# buffer.net
KiCad netlist of a schematic drawn in Altium Designer
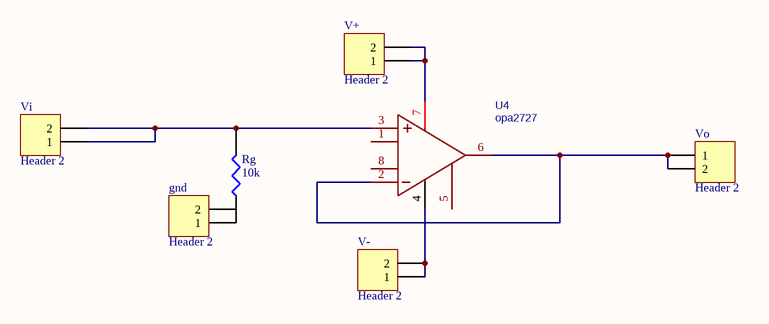
[diagram p0: buffer.SchDoc]

(export (version "E")
  (design (tool "Eeschema 10.0.6"))
  (components
    (comp (ref "gnd")
      (value "Header 2")
      (footprint "SIP2")
      (description "Header, 2-Pin")
      (fields (field (name "PUBLISHER") "Altium Limited"))
      (libsource (lib "Miscellaneous Connectors") (part "Header 2"))
    )
    (comp (ref "Rg")
      (value "10k")
      (footprint "AXIAL0.4")
      (libsource (lib "Miscellaneous Devices") (part "RES1"))
    )
    (comp (ref "U4")
      (value "opa2727")
      (footprint "DIP8")
      (fields (field (name "BOM_MANUFACTURER PART") "AD620ANZ") (field (name "BOM_SUPPLIER PART") "C9680"))
      (libsource (lib "AD620ANZ") (part "AD620ANZ"))
    )
    (comp (ref "V+")
      (value "Header 2")
      (footprint "SIP2")
      (description "Header, 2-Pin")
      (fields (field (name "PUBLISHER") "Altium Limited"))
      (libsource (lib "Miscellaneous Connectors") (part "Header 2"))
    )
    (comp (ref "V-")
      (value "Header 2")
      (footprint "SIP2")
      (description "Header, 2-Pin")
      (fields (field (name "PUBLISHER") "Altium Limited"))
      (libsource (lib "Miscellaneous Connectors") (part "Header 2"))
    )
    (comp (ref "Vi")
      (value "Header 2")
      (footprint "SIP2")
      (description "Header, 2-Pin")
      (fields (field (name "PUBLISHER") "Altium Limited"))
      (libsource (lib "Miscellaneous Connectors") (part "Header 2"))
    )
    (comp (ref "Vo")
      (value "Header 2")
      (footprint "SIP2")
      (description "Header, 2-Pin")
      (fields (field (name "PUBLISHER") "Altium Limited"))
      (libsource (lib "") (part "Header 2_1"))
    )
  )
  (nets
    (net (code "1") (name "Net-(Rg-Pad1)") (class "Default")
      (node (ref "Rg") (pin "1") (pinfunction "1_1") (pintype "passive"))
      (node (ref "gnd") (pin "1") (pinfunction "1_1") (pintype "passive"))
    )
    (net (code "2") (name "Net-(U4-+IN)") (class "Default")
      (node (ref "Rg") (pin "2") (pinfunction "2_2") (pintype "passive"))
      (node (ref "U4") (pin "3") (pinfunction "+IN_3") (pintype "passive"))
      (node (ref "Vi") (pin "1") (pinfunction "1_1") (pintype "passive"))
      (node (ref "Vi") (pin "2") (pinfunction "2_2") (pintype "passive"))
    )
    (net (code "3") (name "Net-(U4-+VS)") (class "Default")
      (node (ref "U4") (pin "7") (pinfunction "+VS_7") (pintype "passive"))
      (node (ref "V+") (pin "1") (pinfunction "1_1") (pintype "passive"))
      (node (ref "V+") (pin "2") (pinfunction "2_2") (pintype "passive"))
    )
    (net (code "4") (name "Net-(U4--IN)") (class "Default")
      (node (ref "U4") (pin "2") (pinfunction "-IN_2") (pintype "passive"))
      (node (ref "U4") (pin "6") (pinfunction "OUTPUT_6") (pintype "passive"))
      (node (ref "Vo") (pin "1") (pinfunction "1_1") (pintype "passive"))
      (node (ref "Vo") (pin "2") (pinfunction "2_2") (pintype "passive"))
    )
    (net (code "5") (name "Net-(U4--VS)") (class "Default")
      (node (ref "U4") (pin "4") (pinfunction "-VS_4") (pintype "passive"))
      (node (ref "V-") (pin "1") (pinfunction "1_1") (pintype "passive"))
      (node (ref "V-") (pin "2") (pinfunction "2_2") (pintype "passive"))
    )
    (net (code "6") (name "unconnected-(U4-REF-Pad5)") (class "Default")
      (node (ref "U4") (pin "5") (pinfunction "REF_5") (pintype "passive"))
    )
    (net (code "7") (name "unconnected-(U4-RG-Pad1)") (class "Default")
      (node (ref "U4") (pin "1") (pinfunction "RG_1") (pintype "passive"))
    )
    (net (code "8") (name "unconnected-(U4-RG-Pad8)") (class "Default")
      (node (ref "U4") (pin "8") (pinfunction "RG_8") (pintype "passive"))
    )
    (net (code "9") (name "unconnected-(gnd-Pad2)") (class "Default")
      (node (ref "gnd") (pin "2") (pinfunction "2_2") (pintype "passive"))
    )
  )
)
